# klon.net
KiCad netlist of a schematic drawn in EAGLE
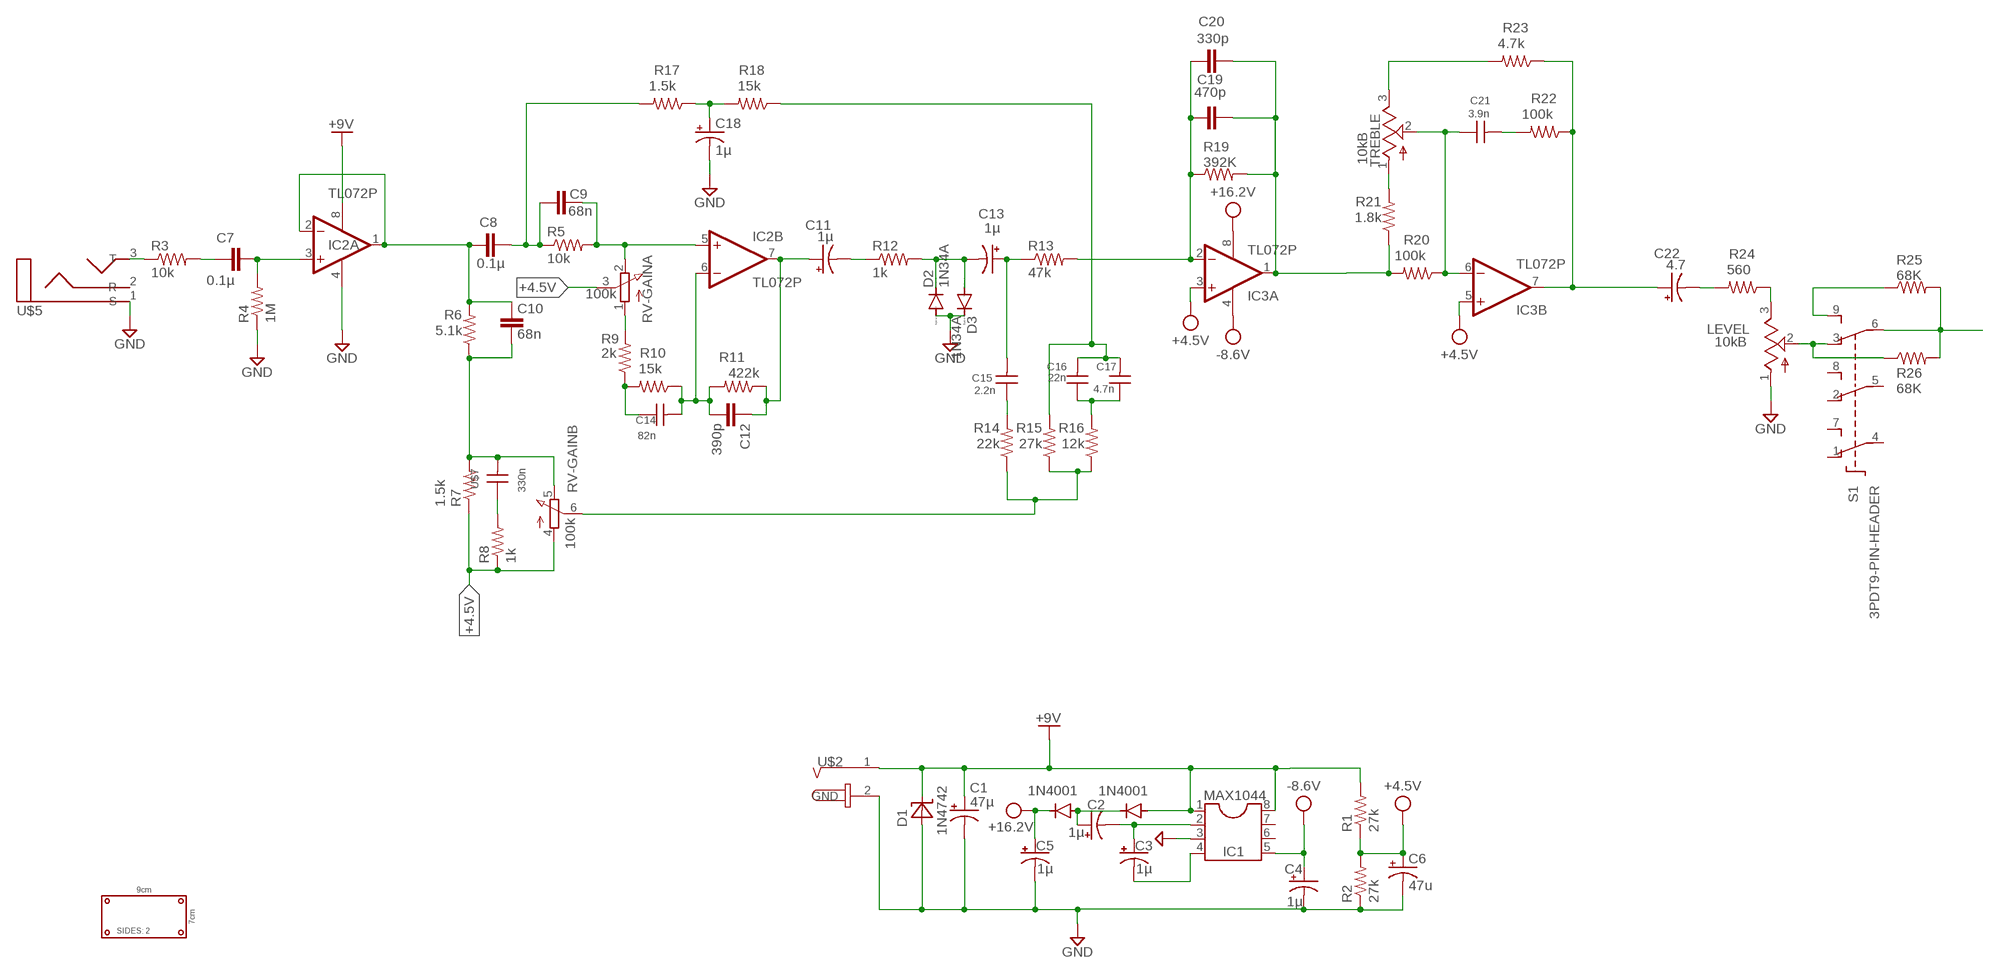
[diagram p0: schematic, sheet 1]

(export (version "E")
  (design (tool "Eeschema 10.0.6"))
  (components
    (comp (ref "C1")
      (value "47µ")
      (footprint "eagle-import:C-E-0.1_0.15")
      (libsource (lib "eagle-import") (part "C-E0.1_0.15"))
    )
    (comp (ref "C2")
      (value "1µ")
      (footprint "eagle-import:C-E-0.1_0.15")
      (libsource (lib "eagle-import") (part "C-E0.1_0.15"))
    )
    (comp (ref "C3")
      (value "1µ")
      (footprint "eagle-import:C-E-0.1_0.15")
      (libsource (lib "eagle-import") (part "C-E0.1_0.15"))
    )
    (comp (ref "C4")
      (value "1µ")
      (footprint "eagle-import:C-E-0.1_0.15")
      (libsource (lib "eagle-import") (part "C-E0.1_0.15"))
    )
    (comp (ref "C5")
      (value "1µ")
      (footprint "eagle-import:C-E-0.1_0.15")
      (libsource (lib "eagle-import") (part "C-E0.1_0.15"))
    )
    (comp (ref "C6")
      (value "47u")
      (footprint "eagle-import:C-E-0.1_0.15")
      (libsource (lib "eagle-import") (part "C-E0.1_0.15"))
    )
    (comp (ref "C7")
      (value "0.1µ")
      (footprint "eagle-import:C10B5")
      (libsource (lib "eagle-import") (part "C10/5"))
    )
    (comp (ref "C8")
      (value "0.1µ")
      (footprint "eagle-import:C10B5")
      (libsource (lib "eagle-import") (part "C10/5"))
    )
    (comp (ref "C9")
      (value "68n")
      (footprint "eagle-import:C10B5")
      (libsource (lib "eagle-import") (part "C10/5"))
    )
    (comp (ref "C10")
      (value "68n")
      (footprint "eagle-import:C10B5")
      (libsource (lib "eagle-import") (part "C10/5"))
    )
    (comp (ref "C11")
      (value "1µ")
      (footprint "eagle-import:C-E-0.1_0.15")
      (libsource (lib "eagle-import") (part "C-E0.1_0.15"))
    )
    (comp (ref "C12")
      (value "390p")
      (footprint "eagle-import:C-C-0.1_0.05")
      (libsource (lib "eagle-import") (part "C-CERAMICC-C-0.1_0.05"))
    )
    (comp (ref "C13")
      (value "1µ")
      (footprint "eagle-import:C-E-0.1_0.15")
      (libsource (lib "eagle-import") (part "C-E0.1_0.15"))
    )
    (comp (ref "C14")
      (value "82n")
      (footprint "eagle-import:C-PP-0.6_0.2")
      (libsource (lib "eagle-import") (part "C-PP_0.60.2W"))
    )
    (comp (ref "C15")
      (value "2.2n")
      (footprint "eagle-import:C-PP-0.4_0.15")
      (libsource (lib "eagle-import") (part "C-PP_0.40.15"))
    )
    (comp (ref "C16")
      (value "22n")
      (footprint "eagle-import:C-PP-0.4_0.2")
      (libsource (lib "eagle-import") (part "C-PP_0.40.2"))
    )
    (comp (ref "C17")
      (value "4.7n")
      (footprint "eagle-import:C-PP-0.4_0.2")
      (libsource (lib "eagle-import") (part "C-PP_0.40.2"))
    )
    (comp (ref "C18")
      (value "1µ")
      (footprint "eagle-import:C-E-0.1_0.15")
      (libsource (lib "eagle-import") (part "C-E0.1_0.15"))
    )
    (comp (ref "C19")
      (value "470p")
      (footprint "eagle-import:C-C-0.1_0.05")
      (libsource (lib "eagle-import") (part "C-CERAMICC-C-0.1_0.05"))
    )
    (comp (ref "C20")
      (value "330p")
      (footprint "eagle-import:C-C-0.1_0.05")
      (libsource (lib "eagle-import") (part "C-CERAMICC-C-0.1_0.05"))
    )
    (comp (ref "C21")
      (value "3.9n")
      (footprint "eagle-import:C-PP-0.4_0.1")
      (libsource (lib "eagle-import") (part "C-PP_0.40.1"))
    )
    (comp (ref "C22")
      (value "4.7")
      (footprint "eagle-import:C-E-0.1_0.15")
      (libsource (lib "eagle-import") (part "C-E0.1_0.15"))
    )
    (comp (ref "D1")
      (value "1N4742")
      (footprint "eagle-import:DO41-7.6")
      (fields (field (name "MF") "EIC Semiconductor"))
      (libsource (lib "eagle-import") (part "1N4742"))
    )
    (comp (ref "D2")
      (value "1N34A")
      (footprint "eagle-import:D-7.5")
      (libsource (lib "eagle-import") (part "DIODE-D-7.5"))
    )
    (comp (ref "D3")
      (value "1N34A")
      (footprint "eagle-import:D-7.5")
      (libsource (lib "eagle-import") (part "DIODE-D-7.5"))
    )
    (comp (ref "IC1")
      (value "MAX1044")
      (footprint "eagle-import:DIL08")
      (fields (field (name "MF") "Maxim Integrated"))
      (libsource (lib "eagle-import") (part "MAX1044"))
    )
    (comp (ref "IC2")
      (value "TL072P")
      (footprint "eagle-import:DIL08")
      (libsource (lib "eagle-import") (part "TL072P"))
    )
    (comp (ref "IC3")
      (value "TL072P")
      (footprint "eagle-import:DIL08")
      (libsource (lib "eagle-import") (part "TL072P"))
    )
    (comp (ref "LEVEL")
      (value "10kB")
      (footprint "eagle-import:1X03")
      (libsource (lib "eagle-import") (part "POT-1X"))
    )
    (comp (ref "R1")
      (value "27k")
      (footprint "eagle-import:0204_7")
      (libsource (lib "eagle-import") (part "RESISTOR0204/7"))
    )
    (comp (ref "R2")
      (value "27k")
      (footprint "eagle-import:0204_7")
      (libsource (lib "eagle-import") (part "RESISTOR0204/7"))
    )
    (comp (ref "R3")
      (value "10k")
      (footprint "eagle-import:0204_7")
      (libsource (lib "eagle-import") (part "RESISTOR0204/7"))
    )
    (comp (ref "R4")
      (value "1M")
      (footprint "eagle-import:0204_7")
      (libsource (lib "eagle-import") (part "RESISTOR0204/7"))
    )
    (comp (ref "R5")
      (value "10k")
      (footprint "eagle-import:0204_7")
      (libsource (lib "eagle-import") (part "RESISTOR0204/7"))
    )
    (comp (ref "R6")
      (value "5.1k")
      (footprint "eagle-import:0204_7")
      (libsource (lib "eagle-import") (part "RESISTOR0204/7"))
    )
    (comp (ref "R7")
      (value "1.5k")
      (footprint "eagle-import:0204_7")
      (libsource (lib "eagle-import") (part "RESISTOR0204/7"))
    )
    (comp (ref "R8")
      (value "1k")
      (footprint "eagle-import:0204_7")
      (libsource (lib "eagle-import") (part "RESISTOR0204/7"))
    )
    (comp (ref "R9")
      (value "2k")
      (footprint "eagle-import:0204_7")
      (libsource (lib "eagle-import") (part "RESISTOR0204/7"))
    )
    (comp (ref "R10")
      (value "15k")
      (footprint "eagle-import:0204_7")
      (libsource (lib "eagle-import") (part "RESISTOR0204/7"))
    )
    (comp (ref "R11")
      (value "422k")
      (footprint "eagle-import:0204_7")
      (libsource (lib "eagle-import") (part "RESISTOR0204/7"))
    )
    (comp (ref "R12")
      (value "1k")
      (footprint "eagle-import:0204_7")
      (libsource (lib "eagle-import") (part "RESISTOR0204/7"))
    )
    (comp (ref "R13")
      (value "47k")
      (footprint "eagle-import:0204_7")
      (libsource (lib "eagle-import") (part "RESISTOR0204/7"))
    )
    (comp (ref "R14")
      (value "22k")
      (footprint "eagle-import:0204_7")
      (libsource (lib "eagle-import") (part "RESISTOR0204/7"))
    )
    (comp (ref "R15")
      (value "27k")
      (footprint "eagle-import:0204_7")
      (libsource (lib "eagle-import") (part "RESISTOR0204/7"))
    )
    (comp (ref "R16")
      (value "12k")
      (footprint "eagle-import:0204_7")
      (libsource (lib "eagle-import") (part "RESISTOR0204/7"))
    )
    (comp (ref "R17")
      (value "1.5k")
      (footprint "eagle-import:0204_7")
      (libsource (lib "eagle-import") (part "RESISTOR0204/7"))
    )
    (comp (ref "R18")
      (value "15k")
      (footprint "eagle-import:0204_7")
      (libsource (lib "eagle-import") (part "RESISTOR0204/7"))
    )
    (comp (ref "R19")
      (value "392K")
      (footprint "eagle-import:0204_7")
      (libsource (lib "eagle-import") (part "RESISTOR0204/7"))
    )
    (comp (ref "R20")
      (value "100k")
      (footprint "eagle-import:0204_7")
      (libsource (lib "eagle-import") (part "RESISTOR0204/7"))
    )
    (comp (ref "R21")
      (value "1.8k")
      (footprint "eagle-import:0204_7")
      (libsource (lib "eagle-import") (part "RESISTOR0204/7"))
    )
    (comp (ref "R22")
      (value "100k")
      (footprint "eagle-import:0204_7")
      (libsource (lib "eagle-import") (part "RESISTOR0204/7"))
    )
    (comp (ref "R23")
      (value "4.7k")
      (footprint "eagle-import:0204_7")
      (libsource (lib "eagle-import") (part "RESISTOR0204/7"))
    )
    (comp (ref "R24")
      (value "560")
      (footprint "eagle-import:0204_7")
      (libsource (lib "eagle-import") (part "RESISTOR0204/7"))
    )
    (comp (ref "R25")
      (value "68K")
      (footprint "eagle-import:0204_7")
      (libsource (lib "eagle-import") (part "RESISTOR0204/7"))
    )
    (comp (ref "R26")
      (value "68K")
      (footprint "eagle-import:0204_7")
      (libsource (lib "eagle-import") (part "RESISTOR0204/7"))
    )
    (comp (ref "RV-GAIN")
      (value "100k")
      (footprint "eagle-import:1X06")
      (libsource (lib "eagle-import") (part "POT-2X"))
    )
    (comp (ref "S1")
      (value "3PDT9-PIN-HEADER")
      (footprint "eagle-import:MA09-1")
      (libsource (lib "eagle-import") (part "3PDT9-PIN-HEADER"))
    )
    (comp (ref "TREBLE")
      (value "10kB")
      (footprint "eagle-import:1X03")
      (libsource (lib "eagle-import") (part "POT-1X"))
    )
    (comp (ref "U$1")
      (value "9x7")
      (footprint "eagle-import:9X7_CM")
      (fields (field (name "SIDES") "2") (field (name "WIDTH") "9cm") (field (name "HEIGHT") "7cm"))
      (libsource (lib "eagle-import") (part "GREEN-2-SIDED9X7"))
    )
    (comp (ref "U$2")
      (value "2_1MM-JACK-PLUG")
      (footprint "eagle-import:1X02")
      (libsource (lib "eagle-import") (part "2_1MM-JACK-PLUG"))
    )
    (comp (ref "U$3")
      (value "1N4001")
      (footprint "eagle-import:DO41-7")
      (libsource (lib "eagle-import") (part "1N4001"))
    )
    (comp (ref "U$4")
      (value "1N4001")
      (footprint "eagle-import:DO41-7")
      (libsource (lib "eagle-import") (part "1N4001"))
    )
    (comp (ref "U$5")
      (value "INSTRUMENT-JACKPINS")
      (footprint "eagle-import:1X03")
      (libsource (lib "eagle-import") (part "INSTRUMENT-JACKPINS"))
    )
    (comp (ref "U$7")
      (value "330n")
      (footprint "eagle-import:C-PP-0.6_0.15")
      (libsource (lib "eagle-import") (part "C-PP_0.60.15W"))
    )
  )
  (nets
    (net (code "1") (name "+4.5V") (class "Default")
      (node (ref "C6") (pin "+") (pinfunction "+_+") (pintype "passive"))
      (node (ref "IC3") (pin "3") (pinfunction "+IN_3") (pintype "input"))
      (node (ref "IC3") (pin "5") (pinfunction "+IN_5") (pintype "input"))
      (node (ref "R1") (pin "1") (pinfunction "1_1") (pintype "passive"))
      (node (ref "R2") (pin "2") (pinfunction "2_2") (pintype "passive"))
      (node (ref "R7") (pin "1") (pinfunction "1_1") (pintype "passive"))
      (node (ref "R8") (pin "1") (pinfunction "1_1") (pintype "passive"))
      (node (ref "RV-GAIN") (pin "3") (pinfunction "S_3") (pintype "passive"))
      (node (ref "RV-GAIN") (pin "4") (pinfunction "A_4") (pintype "passive"))
    )
    (net (code "2") (name "+9V") (class "Default")
      (node (ref "C1") (pin "+") (pinfunction "+_+") (pintype "passive"))
      (node (ref "D1") (pin "C") (pinfunction "C_C") (pintype "passive"))
      (node (ref "IC1") (pin "1") (pinfunction "1_1") (pintype "passive"))
      (node (ref "IC1") (pin "8") (pinfunction "8_8") (pintype "passive"))
      (node (ref "IC2") (pin "8") (pinfunction "V+_8") (pintype "power_in"))
      (node (ref "R1") (pin "2") (pinfunction "2_2") (pintype "passive"))
      (node (ref "U$2") (pin "1") (pinfunction "+9V_1") (pintype "power_in"))
      (node (ref "U$4") (pin "A") (pinfunction "A_A") (pintype "passive"))
    )
    (net (code "3") (name "+16.2V") (class "Default")
      (node (ref "C5") (pin "+") (pinfunction "+_+") (pintype "passive"))
      (node (ref "IC3") (pin "8") (pinfunction "V+_8") (pintype "power_in"))
      (node (ref "U$3") (pin "C") (pinfunction "C_C") (pintype "passive"))
    )
    (net (code "4") (name "-8.6V") (class "Default")
      (node (ref "C4") (pin "+") (pinfunction "+_+") (pintype "passive"))
      (node (ref "IC1") (pin "5") (pinfunction "5_5") (pintype "passive"))
      (node (ref "IC3") (pin "4") (pinfunction "V-_4") (pintype "power_in"))
    )
    (net (code "5") (name "GND") (class "Default")
      (node (ref "C1") (pin "-") (pinfunction "-_-") (pintype "passive"))
      (node (ref "C18") (pin "-") (pinfunction "-_-") (pintype "passive"))
      (node (ref "C4") (pin "-") (pinfunction "-_-") (pintype "passive"))
      (node (ref "C5") (pin "-") (pinfunction "-_-") (pintype "passive"))
      (node (ref "C6") (pin "-") (pinfunction "-_-") (pintype "passive"))
      (node (ref "D1") (pin "A") (pinfunction "A_A") (pintype "passive"))
      (node (ref "D2") (pin "A") (pinfunction "A_A") (pintype "passive"))
      (node (ref "D3") (pin "C") (pinfunction "C_C") (pintype "passive"))
      (node (ref "IC1") (pin "3") (pinfunction "3_3") (pintype "passive"))
      (node (ref "IC2") (pin "4") (pinfunction "V-_4") (pintype "power_in"))
      (node (ref "LEVEL") (pin "1") (pinfunction "1_1") (pintype "passive"))
      (node (ref "R2") (pin "1") (pinfunction "1_1") (pintype "passive"))
      (node (ref "R4") (pin "1") (pinfunction "1_1") (pintype "passive"))
      (node (ref "U$2") (pin "2") (pinfunction "GND_2") (pintype "power_in"))
      (node (ref "U$5") (pin "1") (pinfunction "S_1") (pintype "power_in"))
    )
    (net (code "6") (name "Net-(C2-Pad+)") (class "Default")
      (node (ref "C2") (pin "+") (pinfunction "+_+") (pintype "passive"))
      (node (ref "U$3") (pin "A") (pinfunction "A_A") (pintype "passive"))
      (node (ref "U$4") (pin "C") (pinfunction "C_C") (pintype "passive"))
    )
    (net (code "7") (name "Net-(C2-Pad-)") (class "Default")
      (node (ref "C2") (pin "-") (pinfunction "-_-") (pintype "passive"))
      (node (ref "C3") (pin "+") (pinfunction "+_+") (pintype "passive"))
      (node (ref "IC1") (pin "2") (pinfunction "2_2") (pintype "passive"))
    )
    (net (code "8") (name "Net-(C3-Pad-)") (class "Default")
      (node (ref "C3") (pin "-") (pinfunction "-_-") (pintype "passive"))
      (node (ref "IC1") (pin "4") (pinfunction "4_4") (pintype "passive"))
    )
    (net (code "9") (name "Net-(C7-Pad1)") (class "Default")
      (node (ref "C7") (pin "1") (pinfunction "1_1") (pintype "passive"))
      (node (ref "R3") (pin "2") (pinfunction "2_2") (pintype "passive"))
    )
    (net (code "10") (name "Net-(C8-Pad2)") (class "Default")
      (node (ref "C8") (pin "2") (pinfunction "2_2") (pintype "passive"))
      (node (ref "C9") (pin "1") (pinfunction "1_1") (pintype "passive"))
      (node (ref "R17") (pin "2") (pinfunction "2_2") (pintype "passive"))
      (node (ref "R5") (pin "1") (pinfunction "1_1") (pintype "passive"))
    )
    (net (code "11") (name "Net-(C11-Pad-)") (class "Default")
      (node (ref "C11") (pin "-") (pinfunction "-_-") (pintype "passive"))
      (node (ref "R12") (pin "1") (pinfunction "1_1") (pintype "passive"))
    )
    (net (code "12") (name "Net-(C13-Pad+)") (class "Default")
      (node (ref "C13") (pin "+") (pinfunction "+_+") (pintype "passive"))
      (node (ref "C15") (pin "2") (pinfunction "2_2") (pintype "passive"))
      (node (ref "R13") (pin "1") (pinfunction "1_1") (pintype "passive"))
    )
    (net (code "13") (name "Net-(C13-Pad-)") (class "Default")
      (node (ref "C13") (pin "-") (pinfunction "-_-") (pintype "passive"))
      (node (ref "D2") (pin "C") (pinfunction "C_C") (pintype "passive"))
      (node (ref "D3") (pin "A") (pinfunction "A_A") (pintype "passive"))
      (node (ref "R12") (pin "2") (pinfunction "2_2") (pintype "passive"))
    )
    (net (code "14") (name "Net-(C14-Pad1)") (class "Default")
      (node (ref "C14") (pin "1") (pinfunction "1_1") (pintype "passive"))
      (node (ref "R10") (pin "2") (pinfunction "2_2") (pintype "passive"))
      (node (ref "R9") (pin "1") (pinfunction "1_1") (pintype "passive"))
    )
    (net (code "15") (name "Net-(C15-Pad1)") (class "Default")
      (node (ref "C15") (pin "1") (pinfunction "1_1") (pintype "passive"))
      (node (ref "R14") (pin "2") (pinfunction "2_2") (pintype "passive"))
    )
    (net (code "16") (name "Net-(C16-Pad1)") (class "Default")
      (node (ref "C16") (pin "1") (pinfunction "1_1") (pintype "passive"))
      (node (ref "C17") (pin "1") (pinfunction "1_1") (pintype "passive"))
      (node (ref "R16") (pin "2") (pinfunction "2_2") (pintype "passive"))
    )
    (net (code "17") (name "Net-(C16-Pad2)") (class "Default")
      (node (ref "C16") (pin "2") (pinfunction "2_2") (pintype "passive"))
      (node (ref "C17") (pin "2") (pinfunction "2_2") (pintype "passive"))
      (node (ref "R15") (pin "2") (pinfunction "2_2") (pintype "passive"))
      (node (ref "R18") (pin "1") (pinfunction "1_1") (pintype "passive"))
    )
    (net (code "18") (name "Net-(C18-Pad+)") (class "Default")
      (node (ref "C18") (pin "+") (pinfunction "+_+") (pintype "passive"))
      (node (ref "R17") (pin "1") (pinfunction "1_1") (pintype "passive"))
      (node (ref "R18") (pin "2") (pinfunction "2_2") (pintype "passive"))
    )
    (net (code "19") (name "Net-(C21-Pad2)") (class "Default")
      (node (ref "C21") (pin "2") (pinfunction "2_2") (pintype "passive"))
      (node (ref "R22") (pin "2") (pinfunction "2_2") (pintype "passive"))
    )
    (net (code "20") (name "Net-(C22-Pad-)") (class "Default")
      (node (ref "C22") (pin "-") (pinfunction "-_-") (pintype "passive"))
      (node (ref "R24") (pin "2") (pinfunction "2_2") (pintype "passive"))
    )
    (net (code "21") (name "Net-(IC2A-+IN)") (class "Default")
      (node (ref "C7") (pin "2") (pinfunction "2_2") (pintype "passive"))
      (node (ref "IC2") (pin "3") (pinfunction "+IN_3") (pintype "input"))
      (node (ref "R4") (pin "2") (pinfunction "2_2") (pintype "passive"))
    )
    (net (code "22") (name "Net-(IC2A--IN)") (class "Default")
      (node (ref "C10") (pin "2") (pinfunction "2_2") (pintype "passive"))
      (node (ref "C8") (pin "1") (pinfunction "1_1") (pintype "passive"))
      (node (ref "IC2") (pin "1") (pinfunction "OUT_1") (pintype "output"))
      (node (ref "IC2") (pin "2") (pinfunction "-IN_2") (pintype "input"))
      (node (ref "R6") (pin "2") (pinfunction "2_2") (pintype "passive"))
    )
    (net (code "23") (name "Net-(IC2B-+IN)") (class "Default")
      (node (ref "C9") (pin "2") (pinfunction "2_2") (pintype "passive"))
      (node (ref "IC2") (pin "5") (pinfunction "+IN_5") (pintype "input"))
      (node (ref "R5") (pin "2") (pinfunction "2_2") (pintype "passive"))
      (node (ref "RV-GAIN") (pin "2") (pinfunction "E_2") (pintype "passive"))
    )
    (net (code "24") (name "Net-(IC2B--IN)") (class "Default")
      (node (ref "C12") (pin "2") (pinfunction "2_2") (pintype "passive"))
      (node (ref "C14") (pin "2") (pinfunction "2_2") (pintype "passive"))
      (node (ref "IC2") (pin "6") (pinfunction "-IN_6") (pintype "input"))
      (node (ref "R10") (pin "1") (pinfunction "1_1") (pintype "passive"))
      (node (ref "R11") (pin "2") (pinfunction "2_2") (pintype "passive"))
    )
    (net (code "25") (name "Net-(IC2B-OUT)") (class "Default")
      (node (ref "C11") (pin "+") (pinfunction "+_+") (pintype "passive"))
      (node (ref "C12") (pin "1") (pinfunction "1_1") (pintype "passive"))
      (node (ref "IC2") (pin "7") (pinfunction "OUT_7") (pintype "output"))
      (node (ref "R11") (pin "1") (pinfunction "1_1") (pintype "passive"))
    )
    (net (code "26") (name "Net-(IC3A--IN)") (class "Default")
      (node (ref "C19") (pin "1") (pinfunction "1_1") (pintype "passive"))
      (node (ref "C20") (pin "1") (pinfunction "1_1") (pintype "passive"))
      (node (ref "IC3") (pin "2") (pinfunction "-IN_2") (pintype "input"))
      (node (ref "R13") (pin "2") (pinfunction "2_2") (pintype "passive"))
      (node (ref "R19") (pin "1") (pinfunction "1_1") (pintype "passive"))
    )
    (net (code "27") (name "Net-(IC3A-OUT)") (class "Default")
      (node (ref "C19") (pin "2") (pinfunction "2_2") (pintype "passive"))
      (node (ref "C20") (pin "2") (pinfunction "2_2") (pintype "passive"))
      (node (ref "IC3") (pin "1") (pinfunction "OUT_1") (pintype "output"))
      (node (ref "R19") (pin "2") (pinfunction "2_2") (pintype "passive"))
      (node (ref "R20") (pin "2") (pinfunction "2_2") (pintype "passive"))
      (node (ref "R21") (pin "1") (pinfunction "1_1") (pintype "passive"))
    )
    (net (code "28") (name "Net-(IC3B--IN)") (class "Default")
      (node (ref "C21") (pin "1") (pinfunction "1_1") (pintype "passive"))
      (node (ref "IC3") (pin "6") (pinfunction "-IN_6") (pintype "input"))
      (node (ref "R20") (pin "1") (pinfunction "1_1") (pintype "passive"))
      (node (ref "TREBLE") (pin "2") (pinfunction "2_2") (pintype "passive"))
    )
    (net (code "29") (name "Net-(IC3B-OUT)") (class "Default")
      (node (ref "C22") (pin "+") (pinfunction "+_+") (pintype "passive"))
      (node (ref "IC3") (pin "7") (pinfunction "OUT_7") (pintype "output"))
      (node (ref "R22") (pin "1") (pinfunction "1_1") (pintype "passive"))
      (node (ref "R23") (pin "1") (pinfunction "1_1") (pintype "passive"))
    )
    (net (code "30") (name "Net-(LEVEL-Pad3)") (class "Default")
      (node (ref "LEVEL") (pin "3") (pinfunction "3_3") (pintype "passive"))
      (node (ref "R24") (pin "1") (pinfunction "1_1") (pintype "passive"))
    )
    (net (code "31") (name "Net-(R8-Pad2)") (class "Default")
      (node (ref "R8") (pin "2") (pinfunction "2_2") (pintype "passive"))
      (node (ref "U$7") (pin "1") (pinfunction "1_1") (pintype "passive"))
    )
    (net (code "32") (name "Net-(R21-Pad2)") (class "Default")
      (node (ref "R21") (pin "2") (pinfunction "2_2") (pintype "passive"))
      (node (ref "TREBLE") (pin "1") (pinfunction "1_1") (pintype "passive"))
    )
    (net (code "33") (name "Net-(R23-Pad2)") (class "Default")
      (node (ref "R23") (pin "2") (pinfunction "2_2") (pintype "passive"))
      (node (ref "TREBLE") (pin "3") (pinfunction "3_3") (pintype "passive"))
    )
    (net (code "34") (name "Net-(RV-GAINA-A)") (class "Default")
      (node (ref "R9") (pin "2") (pinfunction "2_2") (pintype "passive"))
      (node (ref "RV-GAIN") (pin "1") (pinfunction "A_1") (pintype "passive"))
    )
    (net (code "35") (name "Net-(RV-GAINB-E)") (class "Default")
      (node (ref "C10") (pin "1") (pinfunction "1_1") (pintype "passive"))
      (node (ref "R6") (pin "1") (pinfunction "1_1") (pintype "passive"))
      (node (ref "R7") (pin "2") (pinfunction "2_2") (pintype "passive"))
      (node (ref "RV-GAIN") (pin "5") (pinfunction "E_5") (pintype "passive"))
      (node (ref "U$7") (pin "2") (pinfunction "2_2") (pintype "passive"))
    )
    (net (code "36") (name "Net-(RV-GAINB-S)") (class "Default")
      (node (ref "R14") (pin "1") (pinfunction "1_1") (pintype "passive"))
      (node (ref "R15") (pin "1") (pinfunction "1_1") (pintype "passive"))
      (node (ref "R16") (pin "1") (pinfunction "1_1") (pintype "passive"))
      (node (ref "RV-GAIN") (pin "6") (pinfunction "S_6") (pintype "passive"))
    )
    (net (code "37") (name "Net-(S1-O3)") (class "Default")
      (node (ref "LEVEL") (pin "2") (pinfunction "2_2") (pintype "passive"))
      (node (ref "R26") (pin "1") (pinfunction "1_1") (pintype "passive"))
      (node (ref "S1") (pin "3") (pinfunction "O3_3") (pintype "passive"))
    )
    (net (code "38") (name "Net-(S1-P3)") (class "Default")
      (node (ref "R25") (pin "2") (pinfunction "2_2") (pintype "passive"))
      (node (ref "R26") (pin "2") (pinfunction "2_2") (pintype "passive"))
      (node (ref "S1") (pin "6") (pinfunction "P3_6") (pintype "passive"))
    )
    (net (code "39") (name "Net-(S1-S3)") (class "Default")
      (node (ref "R25") (pin "1") (pinfunction "1_1") (pintype "passive"))
      (node (ref "S1") (pin "9") (pinfunction "S3_9") (pintype "passive"))
    )
    (net (code "40") (name "Net-(U$5-T)") (class "Default")
      (node (ref "R3") (pin "1") (pinfunction "1_1") (pintype "passive"))
      (node (ref "U$5") (pin "3") (pinfunction "T_3") (pintype "bidirectional"))
    )
    (net (code "41") (name "unconnected-(IC1-Pad6)") (class "Default")
      (node (ref "IC1") (pin "6") (pinfunction "6_6") (pintype "passive"))
    )
    (net (code "42") (name "unconnected-(IC1-Pad7)") (class "Default")
      (node (ref "IC1") (pin "7") (pinfunction "7_7") (pintype "passive"))
    )
    (net (code "43") (name "unconnected-(S1-O1-Pad1)") (class "Default")
      (node (ref "S1") (pin "1") (pinfunction "O1_1") (pintype "passive"))
    )
    (net (code "44") (name "unconnected-(S1-O2-Pad2)") (class "Default")
      (node (ref "S1") (pin "2") (pinfunction "O2_2") (pintype "passive"))
    )
    (net (code "45") (name "unconnected-(S1-P1-Pad4)") (class "Default")
      (node (ref "S1") (pin "4") (pinfunction "P1_4") (pintype "passive"))
    )
    (net (code "46") (name "unconnected-(S1-P2-Pad5)") (class "Default")
      (node (ref "S1") (pin "5") (pinfunction "P2_5") (pintype "passive"))
    )
    (net (code "47") (name "unconnected-(S1-S1-Pad7)") (class "Default")
      (node (ref "S1") (pin "7") (pinfunction "S1_7") (pintype "passive"))
    )
    (net (code "48") (name "unconnected-(S1-S2-Pad8)") (class "Default")
      (node (ref "S1") (pin "8") (pinfunction "S2_8") (pintype "passive"))
    )
    (net (code "49") (name "unconnected-(U$5-R-Pad2)") (class "Default")
      (node (ref "U$5") (pin "2") (pinfunction "R_2") (pintype "bidirectional"))
    )
  )
)
